# SAMW25_Xplained_Pro_WIFI_module.net
KiCad netlist of a schematic drawn in Altium Designer
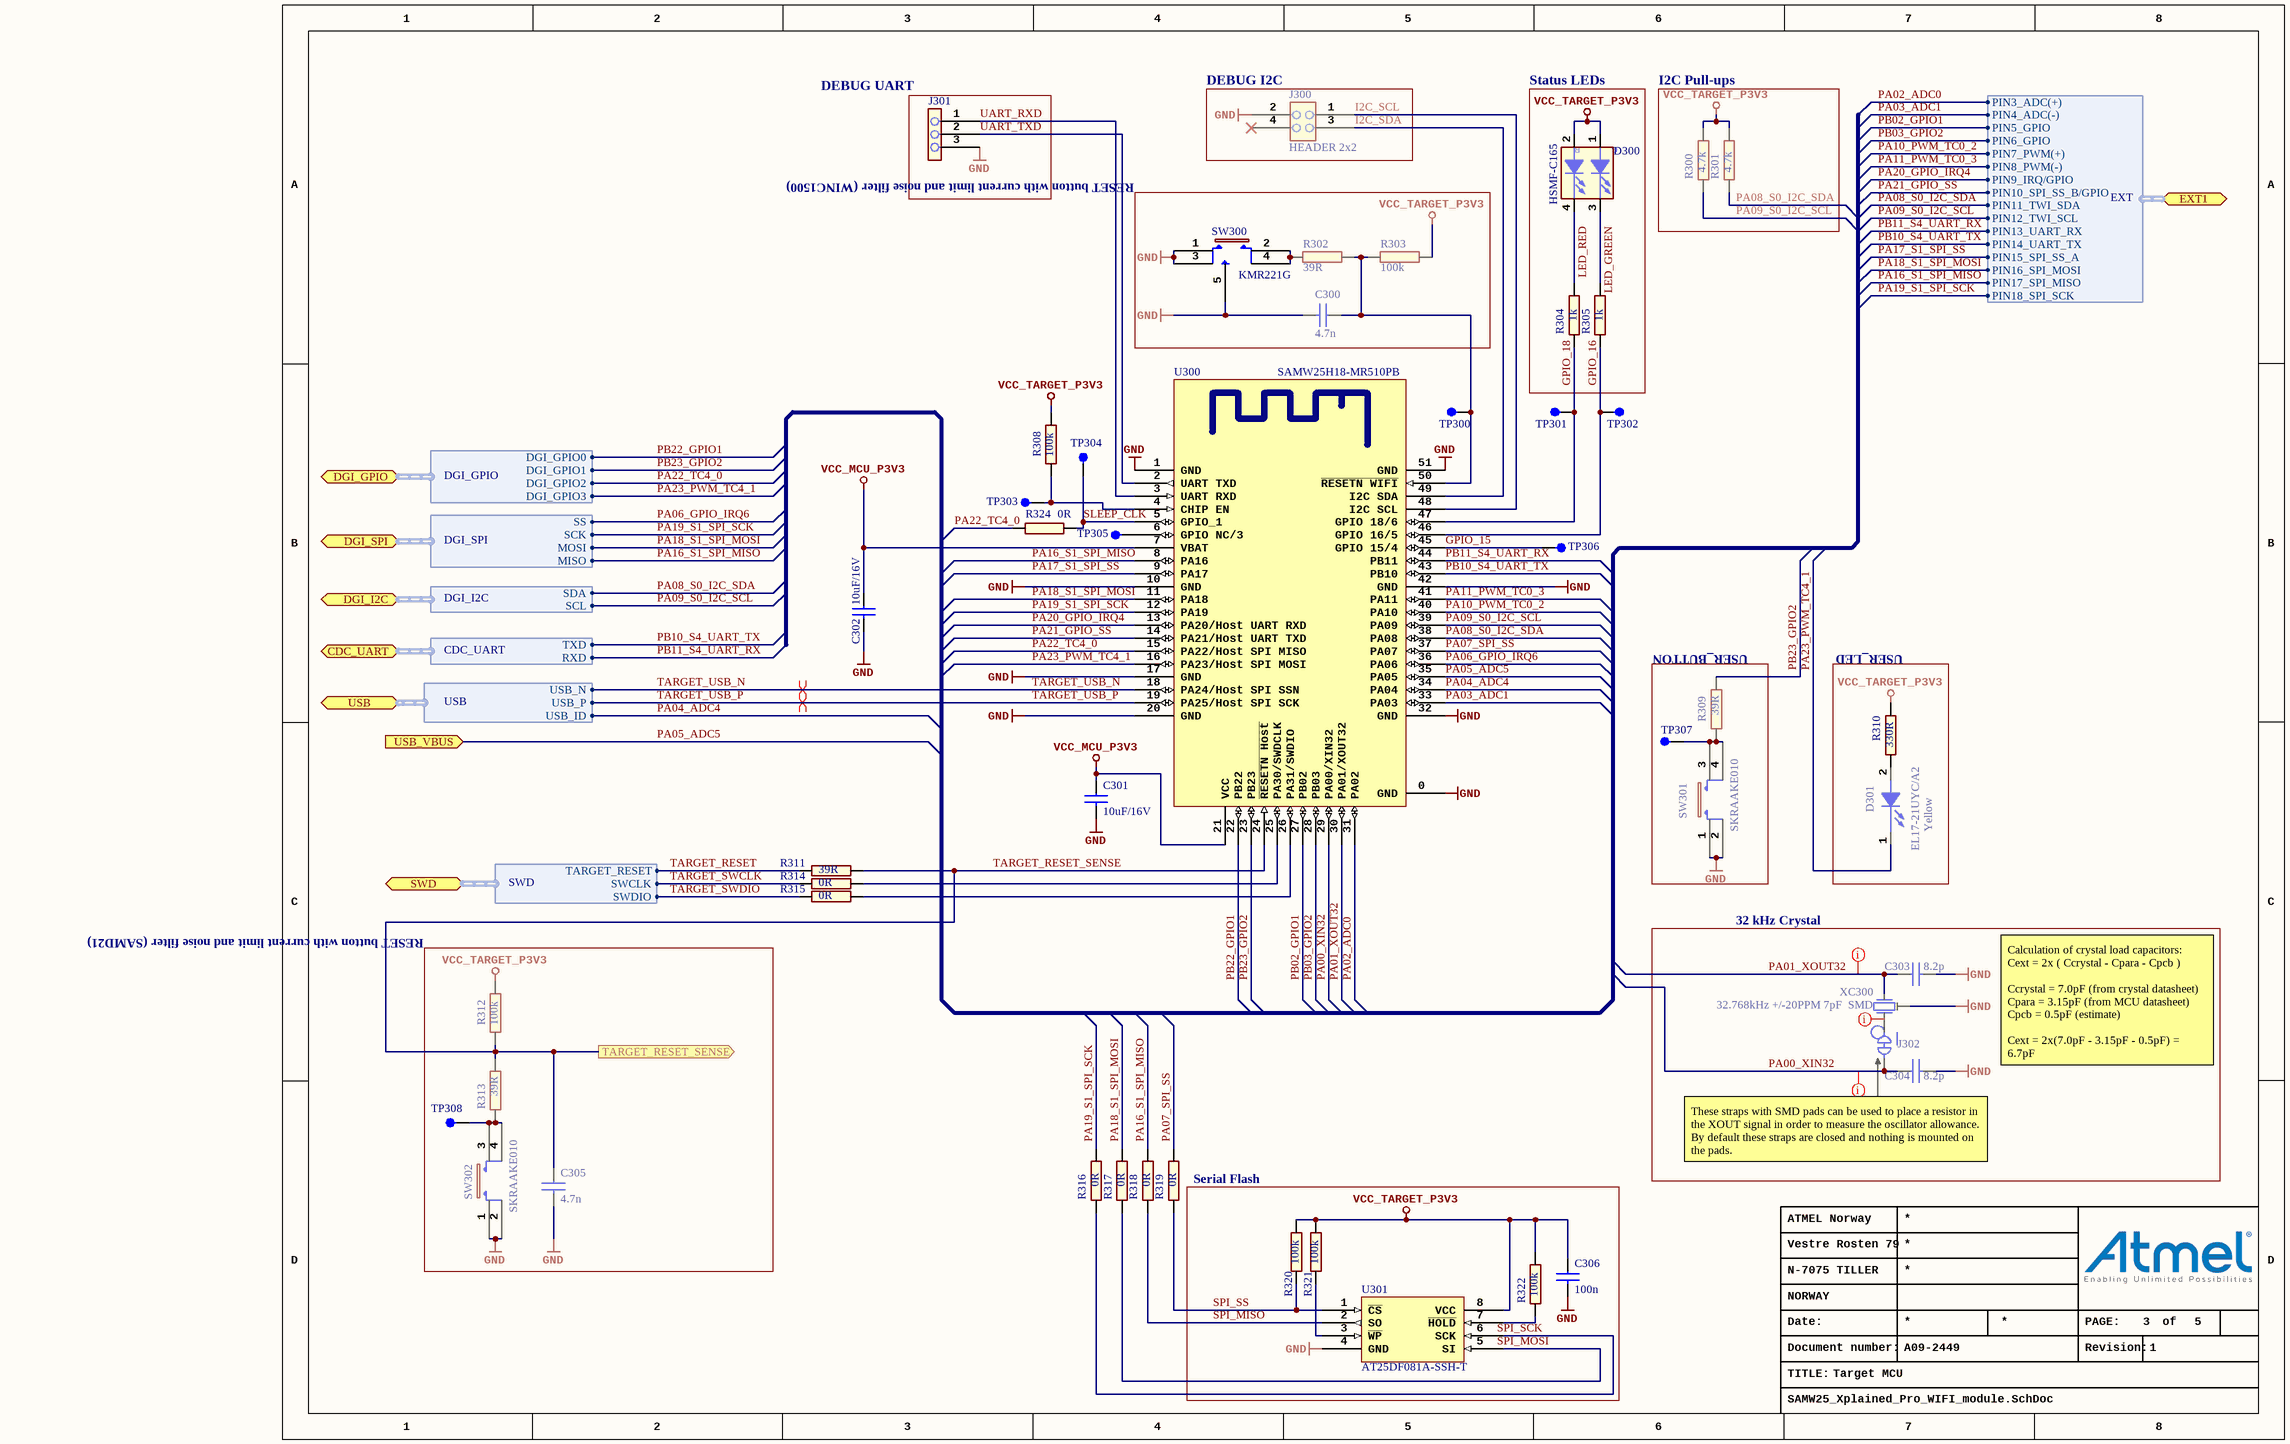
[diagram p0: SAMW25_Xplained_Pro_WIFI_module.SchDoc]

(export (version "E")
  (design (tool "Eeschema 10.0.6"))
  (components
    (comp (ref "C300")
      (value "4.7n")
      (footprint "AP1-00001")
      (description "Ceramic capacitor, SMD 0402, X7R, 16V, +/-10 %")
      (fields
        (field (name "MANUFACTURER") "NIC Components Corp.")
        (field (name "MPN") "NMC0402X7R472K25TRPF")
        (field (name "VERIFIED BY") "Lars Helge Mo")
      )
      (libsource (lib "AltiumDbLib") (part "CAP-NONPOL"))
    )
    (comp (ref "C301")
      (value "10uF/16V")
      (footprint "AP1-00039")
      (description "Ceramic capacitor, SMD 0603, X5R, 16V, 10UF ± 20% (High Density)")
      (fields
        (field (name "TOLERANCE") "­± 20%")
        (field (name "MANUFACTURER") "Taiyo Yuden")
        (field (name "VERIFIED BY") "Lars Helge Mo")
      )
      (libsource (lib "AltiumDbLib") (part "CAP-NONPOL"))
    )
    (comp (ref "C302")
      (value "10uF/16V")
      (footprint "AP1-00039")
      (description "Ceramic capacitor, SMD 0603, X5R, 16V, 10UF ± 20% (High Density)")
      (fields
        (field (name "TOLERANCE") "­± 20%")
        (field (name "MANUFACTURER") "Taiyo Yuden")
        (field (name "VERIFIED BY") "Lars Helge Mo")
      )
      (libsource (lib "AltiumDbLib") (part "CAP-NONPOL"))
    )
    (comp (ref "C303")
      (value "8.2p")
      (footprint "AP1-00001")
      (description "Ceramic capacitor, SMD 0402, NP0, 50V, +/-5%")
      (fields
        (field (name "TOLERANCE") "50V, +/-5%")
        (field (name "Comment") "CAP-NONPOL")
        (field (name "VERIFIED BY") "Lars Helge Mo")
      )
      (libsource (lib "AltiumDbLib") (part "CAP-NONPOL"))
    )
    (comp (ref "C304")
      (value "8.2p")
      (footprint "AP1-00001")
      (description "Ceramic capacitor, SMD 0402, NP0, 50V, +/-5%")
      (fields
        (field (name "TOLERANCE") "50V, +/-5%")
        (field (name "Comment") "CAP-NONPOL")
        (field (name "VERIFIED BY") "Lars Helge Mo")
      )
      (libsource (lib "AltiumDbLib") (part "CAP-NONPOL"))
    )
    (comp (ref "C305")
      (value "4.7n")
      (footprint "AP1-00053")
      (description "Ceramic capacitor, SMD 0402, X7R, 16V, +/-10 %")
      (fields
        (field (name "MANUFACTURER") "NIC Components Corp.")
        (field (name "MPN") "NMC0402X7R472K25TRPF")
        (field (name "VERIFIED BY") "Lars Helge Mo")
      )
      (libsource (lib "AltiumDbLib") (part "CAP-NONPOL"))
    )
    (comp (ref "C306")
      (value "100n")
      (footprint "AP1-00001")
      (description "Ceramic capacitor, SMD 0402, X7R, 16V, +/-10%")
      (fields
        (field (name "TOLERANCE") "16V, +/-10%")
        (field (name "MANUFACTURER") "Kemet")
        (field (name "VERIFIED BY") "Lars Helge Mo")
      )
      (libsource (lib "AltiumDbLib") (part "CAP-NONPOL"))
    )
    (comp (ref "D300")
      (value "HSMF-C165")
      (footprint "AP4-00132")
      (description "LED, Bicolor, Red/Green, Diffused, 1.6 x 0.8 mm (0603)")
      (fields (field (name "MANUFACTURER") "Avago Technologies") (field (name "Comment") "LED2_2"))
      (libsource (lib "AltiumDbLib") (part "LED2_2"))
    )
    (comp (ref "D301")
      (value "Yellow")
      (footprint "AP4-00013")
      (description "LED, Yellow, Wave length=591nm, SMD 0805, ±70°")
      (fields
        (field (name "ALTIUM_VALUE") "EL17-21UYC/A2")
        (field (name "MANUFACTURER") "Everlight")
        (field (name "MPN") "17-21UYC/S530-A3/TR8")
        (field (name "VERIFIED BY") "Sveinung Helgeland")
      )
      (libsource (lib "AltiumDbLib") (part "LED_12"))
    )
    (comp (ref "J300")
      (value "HEADER 2x2")
      (footprint "AP8-00179")
      (description "2x2 pin header, 2.54 mm pitch, Pin-in-Paste THM")
      (fields
        (field (name "MANUFACTURER") "Freber")
        (field (name "MPN") "CD0750142X2")
        (field (name "VERIFIED BY") "Lars Helge Mo")
      )
      (libsource (lib "AltiumDbLib") (part "HEADER 2x2"))
    )
    (comp (ref "J301")
      (value "Same as A08-1614 but with 1mm hole for optimal reflow soldering (no misalignment of the component)")
      (footprint "AP8-00745")
      (description "1x3 pin header, 2.54mm pitch, Pin-in-Paste THM, 1mm hole")
      (fields
        (field (name "MANUFACTURER") "SAMTEC")
        (field (name "MPN") "HMTSW-103-23-F-S-237")
        (field (name "VERIFIED BY") "Lars Helge Mo")
      )
      (libsource (lib "AltiumDbLib") (part "HEADER 1x3"))
    )
    (comp (ref "J302")
      (value "SMD-STRAP_CLOSED")
      (footprint "AP8-00595")
      (description "Closed Link 0402")
      (libsource (lib "AltiumDbLib") (part "SMD-STRAP_CLOSED"))
    )
    (comp (ref "R300")
      (value "4.7k")
      (footprint "AP2-00000")
      (description "Thick film resistor, SMD 0402, 1/16W, 1%")
      (fields
        (field (name "TOLERANCE") "1 %")
        (field (name "Comment") "R2")
        (field (name "VERIFIED BY") "Lars Helge Mo")
      )
      (libsource (lib "") (part "R2_2"))
    )
    (comp (ref "R301")
      (value "4.7k")
      (footprint "AP2-00000")
      (description "Thick film resistor, SMD 0402, 1/16W, 1%")
      (fields
        (field (name "TOLERANCE") "1 %")
        (field (name "Comment") "R2")
        (field (name "VERIFIED BY") "Lars Helge Mo")
      )
      (libsource (lib "") (part "R2_2"))
    )
    (comp (ref "R302")
      (value "39R")
      (footprint "AP2-00000")
      (description "Thick film resistor, SMD 0402, 1/16W, 1%")
      (fields
        (field (name "TOLERANCE") "1 %")
        (field (name "Comment") "R2")
        (field (name "VERIFIED BY") "Lars Helge Mo")
      )
      (libsource (lib "") (part "R2_1"))
    )
    (comp (ref "R303")
      (value "100k")
      (footprint "AP2-00000")
      (description "Thick film resistor, SMD 0402, 1/16W, 1%")
      (fields
        (field (name "TOLERANCE") "1 %")
        (field (name "Comment") "R2")
        (field (name "VERIFIED BY") "Lars Helge Mo")
      )
      (libsource (lib "") (part "R2_3"))
    )
    (comp (ref "R304")
      (value "1k")
      (footprint "AP2-00000")
      (description "Thick film resistor, SMD 0402, 1/16W, 1%")
      (fields
        (field (name "TOLERANCE") "1 %")
        (field (name "Comment") "R2")
        (field (name "VERIFIED BY") "Lars Helge Mo")
      )
      (libsource (lib "") (part "R2_2"))
    )
    (comp (ref "R305")
      (value "1k")
      (footprint "AP2-00000")
      (description "Thick film resistor, SMD 0402, 1/16W, 1%")
      (fields
        (field (name "TOLERANCE") "1 %")
        (field (name "Comment") "R2")
        (field (name "VERIFIED BY") "Lars Helge Mo")
      )
      (libsource (lib "") (part "R2_2"))
    )
    (comp (ref "R308")
      (value "100k")
      (footprint "AP2-00000")
      (description "Thick film resistor, SMD 0402, 1/16W, 1%")
      (fields
        (field (name "TOLERANCE") "1 %")
        (field (name "Comment") "R2")
        (field (name "VERIFIED BY") "Lars Helge Mo")
      )
      (libsource (lib "AltiumDbLib") (part "R2"))
    )
    (comp (ref "R309")
      (value "39R")
      (footprint "AP2-00011")
      (description "Thick film resistor, SMD 0402, 1/16W, 1%")
      (fields
        (field (name "TOLERANCE") "1 %")
        (field (name "Comment") "R2")
        (field (name "VERIFIED BY") "Lars Helge Mo")
      )
      (libsource (lib "") (part "R2_4"))
    )
    (comp (ref "R310")
      (value "330R")
      (footprint "AP2-00000")
      (description "Thick film resistor, SMD 0402, 1/16W, 1%")
      (fields
        (field (name "TOLERANCE") "1 %")
        (field (name "Comment") "R2")
        (field (name "VERIFIED BY") "Lars Helge Mo")
      )
      (libsource (lib "AltiumDbLib") (part "R2"))
    )
    (comp (ref "R311")
      (value "39R")
      (footprint "AP2-00011")
      (description "Thick film resistor, SMD 0402, 1/16W, 1%")
      (fields
        (field (name "TOLERANCE") "1 %")
        (field (name "Comment") "R2")
        (field (name "VERIFIED BY") "Lars Helge Mo")
      )
      (libsource (lib "") (part "R2_1"))
    )
    (comp (ref "R312")
      (value "100k")
      (footprint "AP2-00011")
      (description "Thick film resistor, SMD 0402, 1/16W, 1%")
      (fields
        (field (name "TOLERANCE") "1 %")
        (field (name "Comment") "R2")
        (field (name "VERIFIED BY") "Lars Helge Mo")
      )
      (libsource (lib "AltiumDbLib") (part "R2"))
    )
    (comp (ref "R313")
      (value "39R")
      (footprint "AP2-00011")
      (description "Thick film resistor, SMD 0402, 1/16W, 1%")
      (fields
        (field (name "TOLERANCE") "1 %")
        (field (name "Comment") "R2")
        (field (name "VERIFIED BY") "Lars Helge Mo")
      )
      (libsource (lib "") (part "R2_4"))
    )
    (comp (ref "R314")
      (value "0R")
      (footprint "AP2-00000")
      (description "RES 0.0 OHM 1/16W 0402 SMD")
      (fields
        (field (name "TOLERANCE") "1 %")
        (field (name "MPN") "RMCF0402ZT0R00")
        (field (name "VERIFIED BY") "Lars Helge Mo")
      )
      (libsource (lib "") (part "R2_3"))
    )
    (comp (ref "R315")
      (value "0R")
      (footprint "AP2-00000")
      (description "RES 0.0 OHM 1/16W 0402 SMD")
      (fields
        (field (name "TOLERANCE") "1 %")
        (field (name "MPN") "RMCF0402ZT0R00")
        (field (name "VERIFIED BY") "Lars Helge Mo")
      )
      (libsource (lib "") (part "R2_3"))
    )
    (comp (ref "R316")
      (value "0R")
      (footprint "AP2-00000")
      (description "RES 0.0 OHM 1/16W 0402 SMD")
      (fields
        (field (name "TOLERANCE") "1 %")
        (field (name "MPN") "RMCF0402ZT0R00")
        (field (name "VERIFIED BY") "Lars Helge Mo")
      )
      (libsource (lib "AltiumDbLib") (part "R2"))
    )
    (comp (ref "R317")
      (value "0R")
      (footprint "AP2-00000")
      (description "RES 0.0 OHM 1/16W 0402 SMD")
      (fields
        (field (name "TOLERANCE") "1 %")
        (field (name "MPN") "RMCF0402ZT0R00")
        (field (name "VERIFIED BY") "Lars Helge Mo")
      )
      (libsource (lib "AltiumDbLib") (part "R2"))
    )
    (comp (ref "R318")
      (value "0R")
      (footprint "AP2-00000")
      (description "RES 0.0 OHM 1/16W 0402 SMD")
      (fields
        (field (name "TOLERANCE") "1 %")
        (field (name "MPN") "RMCF0402ZT0R00")
        (field (name "VERIFIED BY") "Lars Helge Mo")
      )
      (libsource (lib "AltiumDbLib") (part "R2"))
    )
    (comp (ref "R319")
      (value "0R")
      (footprint "AP2-00000")
      (description "RES 0.0 OHM 1/16W 0402 SMD")
      (fields
        (field (name "TOLERANCE") "1 %")
        (field (name "MPN") "RMCF0402ZT0R00")
        (field (name "VERIFIED BY") "Lars Helge Mo")
      )
      (libsource (lib "AltiumDbLib") (part "R2"))
    )
    (comp (ref "R320")
      (value "100k")
      (footprint "AP2-00000")
      (description "Thick film resistor, SMD 0402, 1/16W, 1%")
      (fields
        (field (name "TOLERANCE") "1 %")
        (field (name "Comment") "R2")
        (field (name "VERIFIED BY") "Lars Helge Mo")
      )
      (libsource (lib "") (part "R2_2"))
    )
    (comp (ref "R321")
      (value "100k")
      (footprint "AP2-00000")
      (description "Thick film resistor, SMD 0402, 1/16W, 1%")
      (fields
        (field (name "TOLERANCE") "1 %")
        (field (name "Comment") "R2")
        (field (name "VERIFIED BY") "Lars Helge Mo")
      )
      (libsource (lib "") (part "R2_2"))
    )
    (comp (ref "R322")
      (value "100k")
      (footprint "AP2-00000")
      (description "Thick film resistor, SMD 0402, 1/16W, 1%")
      (fields
        (field (name "TOLERANCE") "1 %")
        (field (name "Comment") "R2")
        (field (name "VERIFIED BY") "Lars Helge Mo")
      )
      (libsource (lib "AltiumDbLib") (part "R2"))
    )
    (comp (ref "R324")
      (value "0R")
      (footprint "AP2-00011")
      (description "Thick film resistor, SMD 0402, 1/16W, 1%")
      (fields
        (field (name "TOLERANCE") "1 %")
        (field (name "Comment") "R2")
        (field (name "VERIFIED BY") "Lars Helge Mo")
      )
      (libsource (lib "") (part "R2_3"))
    )
    (comp (ref "SW300")
      (value "KMR221G")
      (footprint "AP8-00274")
      (description "Microminiature Tact Switch for SMT")
      (fields
        (field (name "MANUFACTURER") "ITT cannon")
        (field (name "Comment") "PUSHBUTTON2")
        (field (name "VERIFIED BY") "Ketil Skjerve")
      )
      (libsource (lib "AltiumDbLib") (part "PUSHBUTTON2"))
    )
    (comp (ref "SW301")
      (value "SKRAAKE010")
      (footprint "AP8-00137")
      (description "6.2x6.2 mm SMD tact switch, same as A08-0091 but less force is needed")
      (fields
        (field (name "MANUFACTURER") "ALPS")
        (field (name "Comment") "Can be ordered in low volumes from Mouser")
        (field (name "VERIFIED BY") "Ketil Skjerve")
      )
      (libsource (lib "AltiumDbLib") (part "PUSHBUTTON1"))
    )
    (comp (ref "SW302")
      (value "SKRAAKE010")
      (footprint "AP8-00137")
      (description "6.2x6.2 mm SMD tact switch, same as A08-0091 but less force is needed")
      (fields
        (field (name "MANUFACTURER") "ALPS")
        (field (name "Comment") "Can be ordered in low volumes from Mouser")
        (field (name "VERIFIED BY") "Ketil Skjerve")
      )
      (libsource (lib "AltiumDbLib") (part "PUSHBUTTON1"))
    )
    (comp (ref "TP300")
      (value "TESTPOINT")
      (footprint "AP8-00256")
      (description "Hole for user grid with 1.27 mm pitch, 1x1 mm pad")
      (fields (field (name "VERIFIED BY") "Sveinung Helgeland"))
      (libsource (lib "AltiumDbLib") (part "TESTPOINT"))
    )
    (comp (ref "TP301")
      (value "TESTPOINT")
      (footprint "AP8-00256")
      (description "Hole for user grid with 1.27 mm pitch, 1x1 mm pad")
      (fields (field (name "VERIFIED BY") "Sveinung Helgeland"))
      (libsource (lib "AltiumDbLib") (part "TESTPOINT"))
    )
    (comp (ref "TP302")
      (value "TESTPOINT")
      (footprint "AP8-00256")
      (description "Hole for user grid with 1.27 mm pitch, 1x1 mm pad")
      (fields (field (name "VERIFIED BY") "Sveinung Helgeland"))
      (libsource (lib "AltiumDbLib") (part "TESTPOINT"))
    )
    (comp (ref "TP303")
      (value "TESTPOINT")
      (footprint "AP8-00256")
      (description "Hole for user grid with 1.27 mm pitch, 1x1 mm pad")
      (fields (field (name "VERIFIED BY") "Sveinung Helgeland"))
      (libsource (lib "AltiumDbLib") (part "TESTPOINT"))
    )
    (comp (ref "TP304")
      (value "TESTPOINT")
      (footprint "AP8-00256")
      (description "Hole for user grid with 1.27 mm pitch, 1x1 mm pad")
      (fields (field (name "VERIFIED BY") "Sveinung Helgeland"))
      (libsource (lib "AltiumDbLib") (part "TESTPOINT"))
    )
    (comp (ref "TP305")
      (value "TESTPOINT")
      (footprint "AP8-00256")
      (description "Hole for user grid with 1.27 mm pitch, 1x1 mm pad")
      (fields (field (name "VERIFIED BY") "Sveinung Helgeland"))
      (libsource (lib "AltiumDbLib") (part "TESTPOINT"))
    )
    (comp (ref "TP306")
      (value "TESTPOINT")
      (footprint "AP8-00256")
      (description "Hole for user grid with 1.27 mm pitch, 1x1 mm pad")
      (fields (field (name "VERIFIED BY") "Sveinung Helgeland"))
      (libsource (lib "AltiumDbLib") (part "TESTPOINT"))
    )
    (comp (ref "TP307")
      (value "TESTPOINT")
      (footprint "AP8-00010")
      (description "Single SMD testpad")
      (fields (field (name "VERIFIED BY") "Sveinung Helgeland"))
      (libsource (lib "AltiumDbLib") (part "TESTPOINT"))
    )
    (comp (ref "TP308")
      (value "TESTPOINT")
      (footprint "AP8-00010")
      (description "Single SMD testpad")
      (fields (field (name "VERIFIED BY") "Sveinung Helgeland"))
      (libsource (lib "AltiumDbLib") (part "TESTPOINT"))
    )
    (comp (ref "U300")
      (value "SAMW25H18-MR510PB")
      (footprint "AP9-00132")
      (description "IEEE 802.11 b/g/n module with onboard SAMD21G18A-MU and Crypto IC")
      (fields (field (name "MANUFACTURER") "ATMEL") (field (name "MPN") "ATSAMW25H18-MR510PB"))
      (libsource (lib "AltiumDbLib") (part "MR210PA"))
    )
    (comp (ref "U301")
      (value "AT25DF081A-SSH-T")
      (footprint "AP8-00417")
      (description "8Mbit SPI serial flash memory")
      (fields (field (name "MANUFACTURER") "Adesto Technologies") (field (name "Comment") "AT25DF081A"))
      (libsource (lib "AltiumDbLib") (part "AT25DF081A"))
    )
    (comp (ref "XC300")
      (value "32.768kHz +/-20PPM 7pF  SMD")
      (footprint "AP7-00044")
      (description "32k768 crystal, +-20ppm, CL=7pF, max ESR 60kOhm, SMD")
      (fields (field (name "TOLERANCE") "+/- 20 PPM") (field (name "MANUFACTURER") "Micro Crystal"))
      (libsource (lib "AltiumDbLib") (part "CRYSTAL_2P_metal"))
    )
  )
  (nets
    (net (code "8") (name "/GPIO_15") (class "Default")
      (node (ref "TP306") (pin "1") (pinfunction "1_1") (pintype "passive"))
      (node (ref "U300") (pin "45") (pinfunction "GPIO_15/4_45") (pintype "bidirectional"))
    )
    (net (code "9") (name "/GPIO_16") (class "Default")
      (node (ref "R305") (pin "2") (pinfunction "2_2") (pintype "passive"))
      (node (ref "TP302") (pin "1") (pinfunction "1_1") (pintype "passive"))
      (node (ref "U300") (pin "46") (pinfunction "GPIO_16/5_46") (pintype "bidirectional"))
    )
    (net (code "10") (name "/GPIO_18") (class "Default")
      (node (ref "R304") (pin "2") (pinfunction "2_2") (pintype "passive"))
      (node (ref "TP301") (pin "1") (pinfunction "1_1") (pintype "passive"))
      (node (ref "U300") (pin "47") (pinfunction "GPIO_18/6_47") (pintype "bidirectional"))
    )
    (net (code "11") (name "/I2C_SCL") (class "Default")
      (node (ref "J300") (pin "1") (pinfunction "1_1") (pintype "passive"))
      (node (ref "U300") (pin "48") (pinfunction "I2C_SCL_48") (pintype "open_collector"))
    )
    (net (code "12") (name "/I2C_SDA") (class "Default")
      (node (ref "J300") (pin "3") (pinfunction "3_3") (pintype "passive"))
      (node (ref "U300") (pin "49") (pinfunction "I2C_SDA_49") (pintype "open_collector"))
    )
    (net (code "13") (name "/LED_GREEN") (class "Default")
      (node (ref "D300") (pin "3") (pinfunction "CATHODE3_3") (pintype "passive"))
      (node (ref "R305") (pin "1") (pinfunction "1_1") (pintype "passive"))
    )
    (net (code "14") (name "/LED_RED") (class "Default")
      (node (ref "D300") (pin "4") (pinfunction "CATHODE4_4") (pintype "passive"))
      (node (ref "R304") (pin "1") (pinfunction "1_1") (pintype "passive"))
    )
    (net (code "15") (name "/PA00_XIN32") (class "Default")
      (node (ref "C304") (pin "1") (pinfunction "1_1") (pintype "passive"))
      (node (ref "J302") (pin "2") (pinfunction "2_2") (pintype "passive"))
      (node (ref "U300") (pin "29") (pinfunction "PA00/XIN32_29") (pintype "bidirectional"))
    )
    (net (code "16") (name "/PA01_XOUT32") (class "Default")
      (node (ref "C303") (pin "1") (pinfunction "1_1") (pintype "passive"))
      (node (ref "U300") (pin "30") (pinfunction "PA01/XOUT32_30") (pintype "bidirectional"))
      (node (ref "XC300") (pin "1") (pinfunction "1_1") (pintype "passive"))
    )
    (net (code "17") (name "/PA02_ADC0") (class "Default")
      (node (ref "U300") (pin "31") (pinfunction "PA02_31") (pintype "bidirectional"))
    )
    (net (code "18") (name "/PA03_ADC1") (class "Default")
      (node (ref "U300") (pin "33") (pinfunction "PA03_33") (pintype "bidirectional"))
    )
    (net (code "19") (name "/PA04_ADC4") (class "Default")
      (node (ref "U300") (pin "34") (pinfunction "PA04_34") (pintype "bidirectional"))
    )
    (net (code "20") (name "/PA05_ADC5") (class "Default")
      (node (ref "U300") (pin "35") (pinfunction "PA05_35") (pintype "bidirectional"))
    )
    (net (code "21") (name "/PA06_GPIO_IRQ6") (class "Default")
      (node (ref "U300") (pin "36") (pinfunction "PA06_36") (pintype "bidirectional"))
    )
    (net (code "22") (name "/PA07_SPI_SS") (class "Default")
      (node (ref "R319") (pin "2") (pinfunction "2_2") (pintype "passive"))
      (node (ref "U300") (pin "37") (pinfunction "PA07_37") (pintype "bidirectional"))
    )
    (net (code "23") (name "/PA08_S0_I2C_SDA") (class "Default")
      (node (ref "R301") (pin "2") (pinfunction "2_2") (pintype "passive"))
      (node (ref "U300") (pin "38") (pinfunction "PA08_38") (pintype "bidirectional"))
    )
    (net (code "24") (name "/PA09_S0_I2C_SCL") (class "Default")
      (node (ref "R300") (pin "2") (pinfunction "2_2") (pintype "passive"))
      (node (ref "U300") (pin "39") (pinfunction "PA09_39") (pintype "bidirectional"))
    )
    (net (code "25") (name "/PA10_PWM_TC0_2") (class "Default")
      (node (ref "U300") (pin "40") (pinfunction "PA10_40") (pintype "bidirectional"))
    )
    (net (code "26") (name "/PA11_PWM_TC0_3") (class "Default")
      (node (ref "U300") (pin "41") (pinfunction "PA11_41") (pintype "bidirectional"))
    )
    (net (code "27") (name "/PA16_S1_SPI_MISO") (class "Default")
      (node (ref "R318") (pin "2") (pinfunction "2_2") (pintype "passive"))
      (node (ref "U300") (pin "8") (pinfunction "PA16_8") (pintype "bidirectional"))
    )
    (net (code "28") (name "/PA17_S1_SPI_SS") (class "Default")
      (node (ref "U300") (pin "9") (pinfunction "PA17_9") (pintype "bidirectional"))
    )
    (net (code "29") (name "/PA18_S1_SPI_MOSI") (class "Default")
      (node (ref "R317") (pin "2") (pinfunction "2_2") (pintype "passive"))
      (node (ref "U300") (pin "11") (pinfunction "PA18_11") (pintype "bidirectional"))
    )
    (net (code "30") (name "/PA19_S1_SPI_SCK") (class "Default")
      (node (ref "R316") (pin "2") (pinfunction "2_2") (pintype "passive"))
      (node (ref "U300") (pin "12") (pinfunction "PA19_12") (pintype "bidirectional"))
    )
    (net (code "31") (name "/PA20_GPIO_IRQ4") (class "Default")
      (node (ref "U300") (pin "13") (pinfunction "PA20/Host_UART_RXD_13") (pintype "bidirectional"))
    )
    (net (code "32") (name "/PA21_GPIO_SS") (class "Default")
      (node (ref "U300") (pin "14") (pinfunction "PA21/Host_UART_TXD_14") (pintype "bidirectional"))
    )
    (net (code "33") (name "/PA22_TC4_0") (class "Default")
      (node (ref "R324") (pin "1") (pinfunction "1_1") (pintype "passive"))
      (node (ref "U300") (pin "15") (pinfunction "PA22/Host_SPI_MISO_15") (pintype "bidirectional"))
    )
    (net (code "34") (name "/PA23_PWM_TC4_1") (class "Default")
      (node (ref "D301") (pin "1") (pinfunction "CATHODE_1") (pintype "passive"))
      (node (ref "U300") (pin "16") (pinfunction "PA23/Host_SPI_MOSI_16") (pintype "bidirectional"))
    )
    (net (code "35") (name "/PB02_GPIO1") (class "Default")
      (node (ref "U300") (pin "27") (pinfunction "PB02_27") (pintype "bidirectional"))
    )
    (net (code "36") (name "/PB03_GPIO2") (class "Default")
      (node (ref "U300") (pin "28") (pinfunction "PB03_28") (pintype "bidirectional"))
    )
    (net (code "37") (name "/PB10_S4_UART_TX") (class "Default")
      (node (ref "U300") (pin "43") (pinfunction "PB10_43") (pintype "bidirectional"))
    )
    (net (code "38") (name "/PB11_S4_UART_RX") (class "Default")
      (node (ref "U300") (pin "44") (pinfunction "PB11_44") (pintype "bidirectional"))
    )
    (net (code "39") (name "/PB22_GPIO1") (class "Default")
      (node (ref "U300") (pin "22") (pinfunction "PB22_22") (pintype "bidirectional"))
    )
    (net (code "40") (name "/PB23_GPIO2") (class "Default")
      (node (ref "R309") (pin "2") (pinfunction "2_2") (pintype "passive"))
      (node (ref "U300") (pin "23") (pinfunction "PB23_23") (pintype "bidirectional"))
    )
    (net (code "41") (name "/SLEEP_CLK") (class "Default")
      (node (ref "R324") (pin "2") (pinfunction "2_2") (pintype "passive"))
      (node (ref "TP304") (pin "1") (pinfunction "1_1") (pintype "passive"))
      (node (ref "U300") (pin "5") (pinfunction "GPIO_1_5") (pintype "bidirectional"))
    )
    (net (code "42") (name "/SPI_MISO") (class "Default")
      (node (ref "R318") (pin "1") (pinfunction "1_1") (pintype "passive"))
      (node (ref "U301") (pin "2") (pinfunction "SO_2") (pintype "output"))
    )
    (net (code "45") (name "/SPI_SS") (class "Default")
      (node (ref "R319") (pin "1") (pinfunction "1_1") (pintype "passive"))
      (node (ref "R320") (pin "2") (pinfunction "2_2") (pintype "passive"))
      (node (ref "U301") (pin "1") (pinfunction "~{CS}_1") (pintype "input"))
    )
    (net (code "46") (name "/TARGET_RESET") (class "Default")
      (node (ref "R311") (pin "1") (pinfunction "1_1") (pintype "passive"))
    )
    (net (code "47") (name "/TARGET_RESET_SENSE") (class "Default")
      (node (ref "C305") (pin "1") (pinfunction "1_1") (pintype "passive"))
      (node (ref "R311") (pin "2") (pinfunction "2_2") (pintype "passive"))
      (node (ref "R312") (pin "1") (pinfunction "1_1") (pintype "passive"))
      (node (ref "R313") (pin "2") (pinfunction "2_2") (pintype "passive"))
      (node (ref "U300") (pin "24") (pinfunction "~{RESETN_Host}_24") (pintype "input"))
    )
    (net (code "48") (name "/TARGET_SWCLK") (class "Default")
      (node (ref "R314") (pin "1") (pinfunction "1_1") (pintype "passive"))
    )
    (net (code "49") (name "/TARGET_SWDIO") (class "Default")
      (node (ref "R315") (pin "1") (pinfunction "1_1") (pintype "passive"))
    )
    (net (code "50") (name "/TARGET_USB_N") (class "Default")
      (node (ref "U300") (pin "18") (pinfunction "PA24/Host_SPI_SSN_18") (pintype "bidirectional"))
    )
    (net (code "51") (name "/TARGET_USB_P") (class "Default")
      (node (ref "U300") (pin "19") (pinfunction "PA25/Host_SPI_SCK_19") (pintype "bidirectional"))
    )
    (net (code "52") (name "/UART_RXD") (class "Default")
      (node (ref "J301") (pin "1") (pinfunction "1_1") (pintype "passive"))
      (node (ref "U300") (pin "3") (pinfunction "UART_RXD_3") (pintype "input"))
    )
    (net (code "53") (name "/UART_TXD") (class "Default")
      (node (ref "J301") (pin "2") (pinfunction "2_2") (pintype "passive"))
      (node (ref "U300") (pin "2") (pinfunction "UART_TXD_2") (pintype "output"))
    )
    (net (code "61") (name "GND") (class "Default")
      (node (ref "C300") (pin "2") (pinfunction "2_2") (pintype "passive"))
      (node (ref "C301") (pin "2") (pinfunction "2_2") (pintype "passive"))
      (node (ref "C302") (pin "2") (pinfunction "2_2") (pintype "passive"))
      (node (ref "C303") (pin "2") (pinfunction "2_2") (pintype "passive"))
      (node (ref "C304") (pin "2") (pinfunction "2_2") (pintype "passive"))
      (node (ref "C305") (pin "2") (pinfunction "2_2") (pintype "passive"))
      (node (ref "C306") (pin "2") (pinfunction "2_2") (pintype "passive"))
      (node (ref "J300") (pin "2") (pinfunction "2_2") (pintype "passive"))
      (node (ref "J301") (pin "3") (pinfunction "3_3") (pintype "passive"))
      (node (ref "SW300") (pin "1") (pinfunction "1_1") (pintype "passive"))
      (node (ref "SW300") (pin "3") (pinfunction "3_3") (pintype "passive"))
      (node (ref "SW300") (pin "5") (pinfunction "GND_5") (pintype "passive"))
      (node (ref "SW301") (pin "1") (pinfunction "1_1") (pintype "passive"))
      (node (ref "SW301") (pin "2") (pinfunction "2_2") (pintype "passive"))
      (node (ref "SW302") (pin "1") (pinfunction "1_1") (pintype "passive"))
      (node (ref "SW302") (pin "2") (pinfunction "2_2") (pintype "passive"))
      (node (ref "U300") (pin "0") (pinfunction "GND_0") (pintype "power_in"))
      (node (ref "U300") (pin "1") (pinfunction "GND_1") (pintype "power_in"))
      (node (ref "U300") (pin "10") (pinfunction "GND_10") (pintype "power_in"))
      (node (ref "U300") (pin "17") (pinfunction "GND_17") (pintype "power_in"))
      (node (ref "U300") (pin "20") (pinfunction "GND_20") (pintype "power_in"))
      (node (ref "U300") (pin "32") (pinfunction "GND_32") (pintype "power_in"))
      (node (ref "U300") (pin "42") (pinfunction "GND_42") (pintype "power_in"))
      (node (ref "U300") (pin "51") (pinfunction "GND_51") (pintype "power_in"))
      (node (ref "U301") (pin "4") (pinfunction "GND_4") (pintype "power_in"))
      (node (ref "XC300") (pin "3") (pinfunction "3_3") (pintype "passive"))
    )
    (net (code "62") (name "Net-(D301-ANODE)") (class "Default")
      (node (ref "D301") (pin "2") (pinfunction "ANODE_2") (pintype "passive"))
      (node (ref "R310") (pin "1") (pinfunction "1_1") (pintype "passive"))
    )
    (net (code "63") (name "Net-(J302-Pad1)") (class "Default")
      (node (ref "J302") (pin "1") (pinfunction "1_1") (pintype "passive"))
      (node (ref "XC300") (pin "2") (pinfunction "2_2") (pintype "passive"))
    )
    (net (code "64") (name "Net-(R302-Pad1)") (class "Default")
      (node (ref "R302") (pin "1") (pinfunction "1_1") (pintype "passive"))
      (node (ref "SW300") (pin "2") (pinfunction "2_2") (pintype "passive"))
      (node (ref "SW300") (pin "4") (pinfunction "4_4") (pintype "passive"))
    )
    (net (code "65") (name "Net-(R309-Pad1)") (class "Default")
      (node (ref "R309") (pin "1") (pinfunction "1_1") (pintype "passive"))
      (node (ref "SW301") (pin "3") (pinfunction "3_3") (pintype "passive"))
      (node (ref "SW301") (pin "4") (pinfunction "4_4") (pintype "passive"))
      (node (ref "TP307") (pin "1") (pinfunction "1_1") (pintype "passive"))
    )
    (net (code "66") (name "Net-(R313-Pad1)") (class "Default")
      (node (ref "R313") (pin "1") (pinfunction "1_1") (pintype "passive"))
      (node (ref "SW302") (pin "3") (pinfunction "3_3") (pintype "passive"))
      (node (ref "SW302") (pin "4") (pinfunction "4_4") (pintype "passive"))
      (node (ref "TP308") (pin "1") (pinfunction "1_1") (pintype "passive"))
    )
    (net (code "67") (name "Net-(U300-CHIP_EN)") (class "Default")
      (node (ref "R308") (pin "1") (pinfunction "1_1") (pintype "passive"))
      (node (ref "TP303") (pin "1") (pinfunction "1_1") (pintype "passive"))
      (node (ref "U300") (pin "4") (pinfunction "CHIP_EN_4") (pintype "input"))
    )
    (net (code "68") (name "Net-(U300-GPIO_NC{slash}3)") (class "Default")
      (node (ref "TP305") (pin "1") (pinfunction "1_1") (pintype "passive"))
      (node (ref "U300") (pin "6") (pinfunction "GPIO_NC/3_6") (pintype "bidirectional"))
    )
    (net (code "69") (name "Net-(U300-PA30{slash}SWDCLK)") (class "Default")
      (node (ref "R314") (pin "2") (pinfunction "2_2") (pintype "passive"))
      (node (ref "U300") (pin "25") (pinfunction "PA30/SWDCLK_25") (pintype "bidirectional"))
    )
    (net (code "70") (name "Net-(U300-PA31{slash}SWDIO)") (class "Default")
      (node (ref "R315") (pin "2") (pinfunction "2_2") (pintype "passive"))
      (node (ref "U300") (pin "26") (pinfunction "PA31/SWDIO_26") (pintype "bidirectional"))
    )
    (net (code "71") (name "Net-(U300-~{RESETN_WIFI})") (class "Default")
      (node (ref "C300") (pin "1") (pinfunction "1_1") (pintype "passive"))
      (node (ref "R302") (pin "2") (pinfunction "2_2") (pintype "passive"))
      (node (ref "R303") (pin "1") (pinfunction "1_1") (pintype "passive"))
      (node (ref "TP300") (pin "1") (pinfunction "1_1") (pintype "passive"))
      (node (ref "U300") (pin "50") (pinfunction "~{RESETN_WIFI}_50") (pintype "input"))
    )
    (net (code "72") (name "Net-(U301-SCK)") (class "Default")
      (node (ref "R316") (pin "1") (pinfunction "1_1") (pintype "passive"))
      (node (ref "U301") (pin "6") (pinfunction "SCK_6") (pintype "input"))
    )
    (net (code "73") (name "Net-(U301-SI)") (class "Default")
      (node (ref "R317") (pin "1") (pinfunction "1_1") (pintype "passive"))
      (node (ref "U301") (pin "5") (pinfunction "SI_5") (pintype "input"))
    )
    (net (code "74") (name "Net-(U301-~{HOLD})") (class "Default")
      (node (ref "R322") (pin "1") (pinfunction "1_1") (pintype "passive"))
      (node (ref "U301") (pin "7") (pinfunction "~{HOLD}_7") (pintype "input"))
    )
    (net (code "75") (name "Net-(U301-~{WP})") (class "Default")
      (node (ref "R321") (pin "2") (pinfunction "2_2") (pintype "passive"))
      (node (ref "U301") (pin "3") (pinfunction "~{WP}_3") (pintype "input"))
    )
    (net (code "76") (name "VCC_MCU_P3V3") (class "Default")
      (node (ref "C301") (pin "1") (pinfunction "1_1") (pintype "passive"))
      (node (ref "C302") (pin "1") (pinfunction "1_1") (pintype "passive"))
      (node (ref "U300") (pin "21") (pinfunction "VCC_21") (pintype "power_in"))
      (node (ref "U300") (pin "7") (pinfunction "VBAT_7") (pintype "power_in"))
    )
    (net (code "77") (name "VCC_TARGET_P3V3") (class "Default")
      (node (ref "C306") (pin "1") (pinfunction "1_1") (pintype "passive"))
      (node (ref "D300") (pin "1") (pinfunction "ANODE1_1") (pintype "passive"))
      (node (ref "D300") (pin "2") (pinfunction "ANODE2_2") (pintype "passive"))
      (node (ref "R300") (pin "1") (pinfunction "1_1") (pintype "passive"))
      (node (ref "R301") (pin "1") (pinfunction "1_1") (pintype "passive"))
      (node (ref "R303") (pin "2") (pinfunction "2_2") (pintype "passive"))
      (node (ref "R308") (pin "2") (pinfunction "2_2") (pintype "passive"))
      (node (ref "R310") (pin "2") (pinfunction "2_2") (pintype "passive"))
      (node (ref "R312") (pin "2") (pinfunction "2_2") (pintype "passive"))
      (node (ref "R320") (pin "1") (pinfunction "1_1") (pintype "passive"))
      (node (ref "R321") (pin "1") (pinfunction "1_1") (pintype "passive"))
      (node (ref "R322") (pin "2") (pinfunction "2_2") (pintype "passive"))
      (node (ref "U301") (pin "8") (pinfunction "VCC_8") (pintype "power_in"))
    )
    (net (code "78") (name "unconnected-(J300-Pad4)") (class "Default")
      (node (ref "J300") (pin "4") (pinfunction "4_4") (pintype "passive+no_connect"))
    )
  )
)
